# FAT34p.net
KiCad netlist of a schematic drawn in Altium Designer
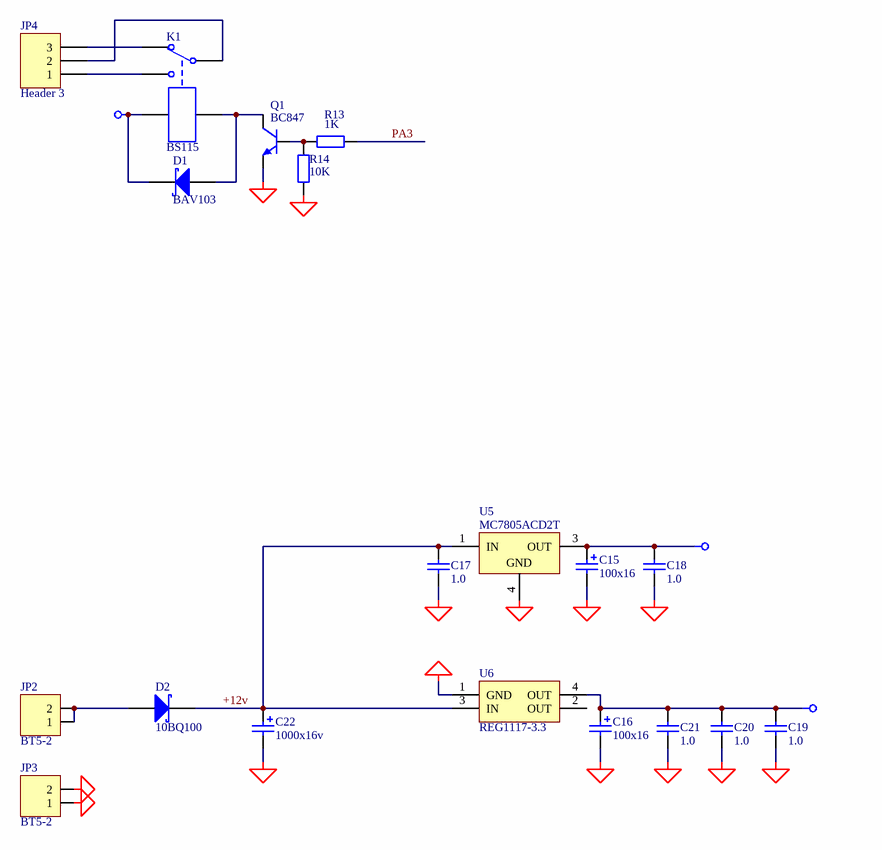
[diagram p0: FAT34p.SchDoc]

(export (version "E")
  (design (tool "Eeschema 10.0.6"))
  (components
    (comp (ref "C15")
      (value "100x16")
      (footprint "el3")
      (description "Polarized Capacitor (Radial)")
      (fields (field (name "MANUFACTURER") "Generic Components") (field (name "PUBLISHER") "Altium Limited"))
      (libsource (lib "BUF") (part "Cap Pol"))
    )
    (comp (ref "C16")
      (value "100x16")
      (footprint "el3")
      (description "Polarized Capacitor (Radial)")
      (fields (field (name "MANUFACTURER") "Generic Components") (field (name "PUBLISHER") "Altium Limited"))
      (libsource (lib "BUF") (part "Cap Pol"))
    )
    (comp (ref "C17")
      (value "Cap")
      (footprint "_1206")
      (description "Capacitor")
      (fields
        (field (name "MANUFACTURER") "Generic Components")
        (field (name "ALTIUM_VALUE") "1.0")
        (field (name "PUBLISHER") "Altium Limited")
      )
      (libsource (lib "BUF") (part "Cap"))
    )
    (comp (ref "C18")
      (value "Cap")
      (footprint "_1206")
      (description "Capacitor")
      (fields
        (field (name "MANUFACTURER") "Generic Components")
        (field (name "ALTIUM_VALUE") "1.0")
        (field (name "PUBLISHER") "Altium Limited")
      )
      (libsource (lib "BUF") (part "Cap"))
    )
    (comp (ref "C19")
      (value "Cap")
      (footprint "_1206")
      (description "Capacitor")
      (fields
        (field (name "MANUFACTURER") "Generic Components")
        (field (name "ALTIUM_VALUE") "1.0")
        (field (name "PUBLISHER") "Altium Limited")
      )
      (libsource (lib "BUF") (part "Cap"))
    )
    (comp (ref "C20")
      (value "Cap")
      (footprint "_1206")
      (description "Capacitor")
      (fields
        (field (name "MANUFACTURER") "Generic Components")
        (field (name "ALTIUM_VALUE") "1.0")
        (field (name "PUBLISHER") "Altium Limited")
      )
      (libsource (lib "BUF") (part "Cap"))
    )
    (comp (ref "C21")
      (value "Cap")
      (footprint "_1206")
      (description "Capacitor")
      (fields
        (field (name "MANUFACTURER") "Generic Components")
        (field (name "ALTIUM_VALUE") "1.0")
        (field (name "PUBLISHER") "Altium Limited")
      )
      (libsource (lib "BUF") (part "Cap"))
    )
    (comp (ref "C22")
      (value "1000x16v")
      (footprint "el5")
      (description "Polarized Capacitor (Radial)")
      (fields (field (name "MANUFACTURER") "Generic Components") (field (name "PUBLISHER") "Altium Limited"))
      (libsource (lib "BUF") (part "Cap Pol1"))
    )
    (comp (ref "D1")
      (value "BAV103")
      (footprint "_1206d")
      (description "Schottky Rectifier")
      (fields
        (field (name "MANUFACTURER") "International Rectifier")
        (field (name "PUBLISHER") "Altium Limited")
      )
      (libsource (lib "IR Discrete Diode") (part "10BQ015"))
    )
    (comp (ref "D2")
      (value "10BQ100")
      (footprint "D_6_3")
      (description "Schottky Rectifier")
      (fields
        (field (name "MANUFACTURER") "International Rectifier")
        (field (name "PUBLISHER") "Altium Limited")
      )
      (libsource (lib "IR Discrete Diode") (part "10BQ015"))
    )
    (comp (ref "JP2")
      (value "BT5-2")
      (footprint "BT5-2-1")
      (description "Header, 3-Pin")
      (fields (field (name "MANUFACTURER") "Generic Components") (field (name "PUBLISHER") "Altium Limited"))
      (libsource (lib "PAL") (part "BT5-2"))
    )
    (comp (ref "JP3")
      (value "BT5-2")
      (footprint "BT5-2-1")
      (description "Header, 3-Pin")
      (fields (field (name "MANUFACTURER") "Generic Components") (field (name "PUBLISHER") "Altium Limited"))
      (libsource (lib "PAL") (part "BT5-2"))
    )
    (comp (ref "JP4")
      (value "Header 3")
      (footprint "BT5-3")
      (description "Header, 3-Pin")
      (fields (field (name "MANUFACTURER") "Generic Components") (field (name "PUBLISHER") "Altium Limited"))
      (libsource (lib "Miscellaneous Connectors") (part "Header 3"))
    )
    (comp (ref "K1")
      (value "BS115")
      (footprint "BS115")
      (description "Single-Pole Dual-Throw Relay")
      (fields (field (name "MANUFACTURER") "Generic Components") (field (name "PUBLISHER") "Altium Limited"))
      (libsource (lib "PAL") (part "BS115"))
    )
    (comp (ref "Q1")
      (value "BC847")
      (footprint "SO-G3")
      (description "General Purpose Transistor NPN Silicon")
      (fields (field (name "MANUFACTURER") "Motorola") (field (name "PUBLISHER") "Altium Limited"))
      (libsource (lib "PAL") (part "BC847ALT1"))
    )
    (comp (ref "R13")
      (value "Res2")
      (footprint "_1206")
      (description "Resistor")
      (fields
        (field (name "MANUFACTURER") "Generic Components")
        (field (name "ALTIUM_VALUE") "1K")
        (field (name "PUBLISHER") "Altium Limited")
      )
      (libsource (lib "Miscellaneous Devices") (part "Res2"))
    )
    (comp (ref "R14")
      (value "Res2")
      (footprint "_1206")
      (description "Resistor")
      (fields
        (field (name "MANUFACTURER") "Generic Components")
        (field (name "ALTIUM_VALUE") "10K")
        (field (name "PUBLISHER") "Altium Limited")
      )
      (libsource (lib "") (part "Res2_1"))
    )
    (comp (ref "U5")
      (value "MC7805ACD2T")
      (footprint "D2PAK")
      (description "Three-Terminal Positive Voltage Regulator")
      (fields (field (name "MANUFACTURER") "ON Semiconductor") (field (name "PUBLISHER") "Altium Limited"))
      (libsource (lib "ON Semi Power Mgt Voltage Regulator") (part "MC7805ACD2T"))
    )
    (comp (ref "U6")
      (value "REG1117-3.3")
      (footprint "SIP-G3/E13")
      (description "800mA and 1A Low Dropout Positive Regulator 2.85V, 3.3V, 5V, and Adjustable")
      (fields (field (name "MANUFACTURER") "Burr-Brown") (field (name "PUBLISHER") "Altium Limited"))
      (libsource (lib "BB Power Mgt Voltage Regulator") (part "REG1117-3.3"))
    )
  )
  (nets
    (net (code "1") (name "+3v3") (class "Default")
      (node (ref "C16") (pin "1") (pinfunction "1_1") (pintype "passive"))
      (node (ref "C19") (pin "2") (pinfunction "2_2") (pintype "passive"))
      (node (ref "C20") (pin "2") (pinfunction "2_2") (pintype "passive"))
      (node (ref "C21") (pin "2") (pinfunction "2_2") (pintype "passive"))
      (node (ref "U6") (pin "4") (pinfunction "OUT_4") (pintype "power_in"))
    )
    (net (code "2") (name "+5v") (class "Default")
      (node (ref "C15") (pin "1") (pinfunction "1_1") (pintype "passive"))
      (node (ref "C18") (pin "2") (pinfunction "2_2") (pintype "passive"))
      (node (ref "U5") (pin "3") (pinfunction "OUT_3") (pintype "power_in"))
    )
    (net (code "3") (name "+12v") (class "Default")
      (node (ref "C17") (pin "2") (pinfunction "2_2") (pintype "passive"))
      (node (ref "C22") (pin "1") (pinfunction "1_1") (pintype "passive"))
      (node (ref "D1") (pin "2") (pinfunction "K_2") (pintype "passive"))
      (node (ref "D2") (pin "2") (pinfunction "K_2") (pintype "passive"))
      (node (ref "K1") (pin "5") (pinfunction "5_5") (pintype "passive"))
      (node (ref "U5") (pin "1") (pinfunction "IN_1") (pintype "power_in"))
      (node (ref "U6") (pin "3") (pinfunction "IN_3") (pintype "power_in"))
    )
    (net (code "4") (name "/PA3") (class "Default")
      (node (ref "R13") (pin "2") (pinfunction "2_2") (pintype "passive"))
    )
    (net (code "5") (name "GND") (class "Default")
      (node (ref "C15") (pin "2") (pinfunction "2_2") (pintype "passive"))
      (node (ref "C16") (pin "2") (pinfunction "2_2") (pintype "passive"))
      (node (ref "C17") (pin "1") (pinfunction "1_1") (pintype "passive"))
      (node (ref "C18") (pin "1") (pinfunction "1_1") (pintype "passive"))
      (node (ref "C19") (pin "1") (pinfunction "1_1") (pintype "passive"))
      (node (ref "C20") (pin "1") (pinfunction "1_1") (pintype "passive"))
      (node (ref "C21") (pin "1") (pinfunction "1_1") (pintype "passive"))
      (node (ref "C22") (pin "2") (pinfunction "2_2") (pintype "passive"))
      (node (ref "JP3") (pin "1") (pinfunction "1_1") (pintype "passive"))
      (node (ref "JP3") (pin "2") (pinfunction "2_2") (pintype "passive"))
      (node (ref "Q1") (pin "2") (pinfunction "E_2") (pintype "passive"))
      (node (ref "R14") (pin "2") (pinfunction "2_2") (pintype "passive"))
      (node (ref "U5") (pin "4") (pinfunction "GND_4") (pintype "power_in"))
      (node (ref "U6") (pin "1") (pinfunction "GND_1") (pintype "power_in"))
    )
    (net (code "6") (name "Net-(D1-A)") (class "Default")
      (node (ref "D1") (pin "1") (pinfunction "A_1") (pintype "passive"))
      (node (ref "K1") (pin "4") (pinfunction "4_4") (pintype "passive"))
      (node (ref "Q1") (pin "3") (pinfunction "C_3") (pintype "passive"))
    )
    (net (code "7") (name "Net-(D2-A)") (class "Default")
      (node (ref "D2") (pin "1") (pinfunction "A_1") (pintype "passive"))
      (node (ref "JP2") (pin "1") (pinfunction "1_1") (pintype "passive"))
      (node (ref "JP2") (pin "2") (pinfunction "2_2") (pintype "passive"))
    )
    (net (code "8") (name "Net-(JP4-Pad1)") (class "Default")
      (node (ref "JP4") (pin "1") (pinfunction "1_1") (pintype "passive"))
      (node (ref "K1") (pin "3") (pinfunction "3_3") (pintype "passive"))
    )
    (net (code "9") (name "Net-(JP4-Pad2)") (class "Default")
      (node (ref "JP4") (pin "2") (pinfunction "2_2") (pintype "passive"))
      (node (ref "K1") (pin "1") (pinfunction "1_1") (pintype "passive"))
    )
    (net (code "10") (name "Net-(JP4-Pad3)") (class "Default")
      (node (ref "JP4") (pin "3") (pinfunction "3_3") (pintype "passive"))
      (node (ref "K1") (pin "2") (pinfunction "2_2") (pintype "passive"))
    )
    (net (code "11") (name "Net-(Q1-B)") (class "Default")
      (node (ref "Q1") (pin "1") (pinfunction "B_1") (pintype "passive"))
      (node (ref "R13") (pin "1") (pinfunction "1_1") (pintype "passive"))
      (node (ref "R14") (pin "1") (pinfunction "1_1") (pintype "passive"))
    )
    (net (code "12") (name "unconnected-(U6-OUT-Pad2)") (class "Default")
      (node (ref "U6") (pin "2") (pinfunction "OUT_2") (pintype "power_in"))
    )
  )
)
